# APX_USB_HUB.net
KiCad netlist of a schematic drawn in EasyEDA
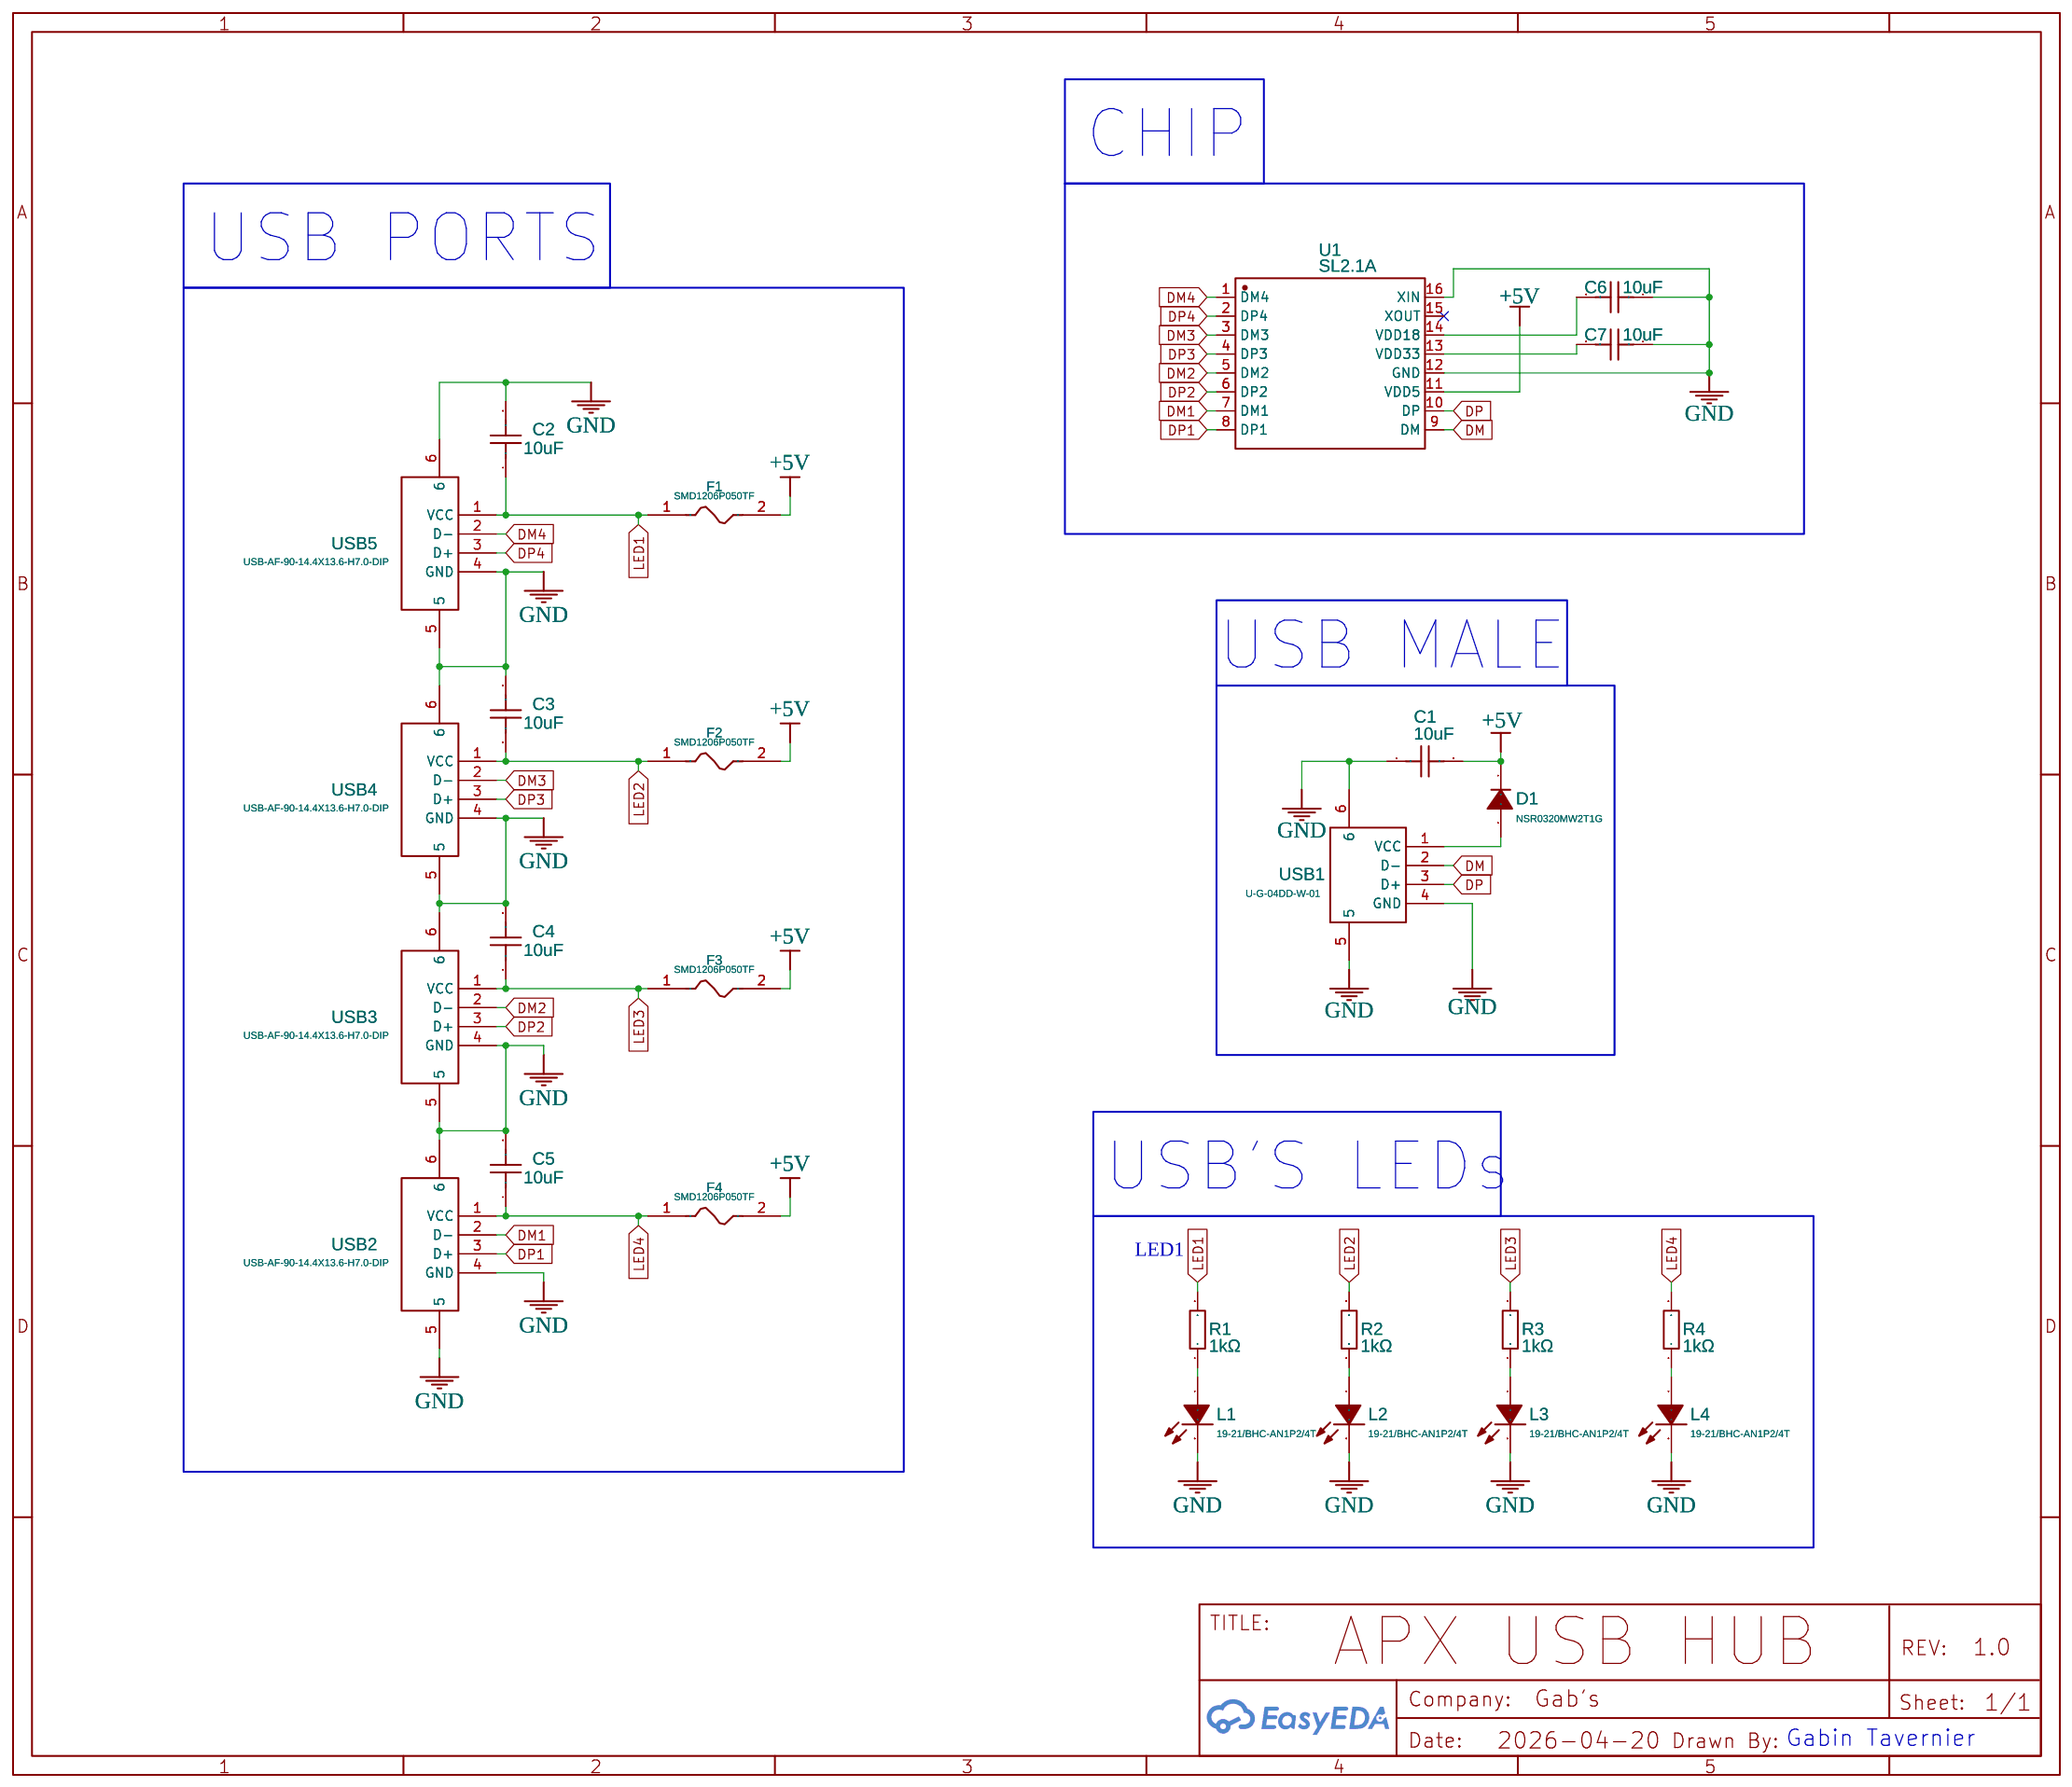
[diagram p0: schematic sheet]

(export (version "E")
  (design (tool "Eeschema 10.0.6"))
  (components
    (comp (ref "C1")
      (value "10uF")
      (fields
        (field (name "Manufacturer Part") "CL10A106KP8NNNC")
        (field (name "Manufacturer") "SAMSUNG(三星)")
      )
      (libsource (lib "") (part "CL10A106KP8NNNC_2"))
    )
    (comp (ref "C2")
      (value "10uF")
      (fields
        (field (name "Manufacturer Part") "CL10A106KP8NNNC")
        (field (name "Manufacturer") "SAMSUNG(三星)")
      )
      (libsource (lib "") (part "CL10A106KP8NNNC"))
    )
    (comp (ref "C3")
      (value "10uF")
      (fields
        (field (name "Manufacturer Part") "CL10A106KP8NNNC")
        (field (name "Manufacturer") "SAMSUNG(三星)")
      )
      (libsource (lib "") (part "CL10A106KP8NNNC"))
    )
    (comp (ref "C4")
      (value "10uF")
      (fields
        (field (name "Manufacturer Part") "CL10A106KP8NNNC")
        (field (name "Manufacturer") "SAMSUNG(三星)")
      )
      (libsource (lib "") (part "CL10A106KP8NNNC"))
    )
    (comp (ref "C5")
      (value "10uF")
      (fields
        (field (name "Manufacturer Part") "CL10A106KP8NNNC")
        (field (name "Manufacturer") "SAMSUNG(三星)")
      )
      (libsource (lib "") (part "CL10A106KP8NNNC"))
    )
    (comp (ref "C6")
      (value "10uF")
      (fields
        (field (name "Manufacturer Part") "CL10A106KP8NNNC")
        (field (name "Manufacturer") "SAMSUNG(三星)")
      )
      (libsource (lib "") (part "CL10A106KP8NNNC_1"))
    )
    (comp (ref "C7")
      (value "10uF")
      (fields
        (field (name "Manufacturer Part") "CL10A106KP8NNNC")
        (field (name "Manufacturer") "SAMSUNG(三星)")
      )
      (libsource (lib "") (part "CL10A106KP8NNNC_1"))
    )
    (comp (ref "D1")
      (value "NSR0320MW2T1G")
      (fields (field (name "Manufacturer") "onsemi(安森美)"))
      (libsource (lib "") (part "NSR0320MW2T1G"))
    )
    (comp (ref "F1")
      (value "SMD1206P050TF")
      (fields (field (name "Manufacturer") "RUILON(瑞隆源)"))
      (libsource (lib "") (part "SMD1206P050TF"))
    )
    (comp (ref "F2")
      (value "SMD1206P050TF")
      (fields (field (name "Manufacturer") "RUILON(瑞隆源)"))
      (libsource (lib "") (part "SMD1206P050TF"))
    )
    (comp (ref "F3")
      (value "SMD1206P050TF")
      (fields (field (name "Manufacturer") "RUILON(瑞隆源)"))
      (libsource (lib "") (part "SMD1206P050TF"))
    )
    (comp (ref "F4")
      (value "SMD1206P050TF")
      (fields (field (name "Manufacturer") "RUILON(瑞隆源)"))
      (libsource (lib "") (part "SMD1206P050TF"))
    )
    (comp (ref "L1")
      (value "19-21/BHC-AN1P2/4T")
      (fields (field (name "Manufacturer") "EVERLIGHT(亿光)"))
      (libsource (lib "") (part "19-21/BHC-AN1P2/4T"))
    )
    (comp (ref "L2")
      (value "19-21/BHC-AN1P2/4T")
      (fields (field (name "Manufacturer") "EVERLIGHT(亿光)"))
      (libsource (lib "") (part "19-21/BHC-AN1P2/4T"))
    )
    (comp (ref "L3")
      (value "19-21/BHC-AN1P2/4T")
      (fields (field (name "Manufacturer") "EVERLIGHT(亿光)"))
      (libsource (lib "") (part "19-21/BHC-AN1P2/4T"))
    )
    (comp (ref "L4")
      (value "19-21/BHC-AN1P2/4T")
      (fields (field (name "Manufacturer") "EVERLIGHT(亿光)"))
      (libsource (lib "") (part "19-21/BHC-AN1P2/4T"))
    )
    (comp (ref "R1")
      (value "1kΩ")
      (fields (field (name "Manufacturer Part") "RC0805FR-071KL") (field (name "Manufacturer") "YAGEO(国巨)"))
      (libsource (lib "") (part "RC0805FR-071KL"))
    )
    (comp (ref "R2")
      (value "1kΩ")
      (fields (field (name "Manufacturer Part") "RC0805FR-071KL") (field (name "Manufacturer") "YAGEO(国巨)"))
      (libsource (lib "") (part "RC0805FR-071KL"))
    )
    (comp (ref "R3")
      (value "1kΩ")
      (fields (field (name "Manufacturer Part") "RC0805FR-071KL") (field (name "Manufacturer") "YAGEO(国巨)"))
      (libsource (lib "") (part "RC0805FR-071KL"))
    )
    (comp (ref "R4")
      (value "1kΩ")
      (fields (field (name "Manufacturer Part") "RC0805FR-071KL") (field (name "Manufacturer") "YAGEO(国巨)"))
      (libsource (lib "") (part "RC0805FR-071KL"))
    )
    (comp (ref "U1")
      (value "SL2.1A")
      (fields (field (name "Manufacturer") "CoreChips(和芯润德)"))
      (libsource (lib "") (part "SL2.1A"))
    )
    (comp (ref "USB1")
      (value "U-G-04DD-W-01")
      (fields (field (name "Manufacturer Part") "U-G-O4DD-W-1") (field (name "Manufacturer") "韩国韩荣"))
      (libsource (lib "") (part "U-G-04DD-W-01"))
    )
    (comp (ref "USB2")
      (value "USB-AF-90-14.4X13.6-H7.0-DIP")
      (fields (field (name "Manufacturer Part") "903-131A1011D10100") (field (name "Manufacturer") "精拓金"))
      (libsource (lib "") (part "USB-AF-90-14.4X13.6-H7.0-DIP"))
    )
    (comp (ref "USB3")
      (value "USB-AF-90-14.4X13.6-H7.0-DIP")
      (fields (field (name "Manufacturer Part") "903-131A1011D10100") (field (name "Manufacturer") "精拓金"))
      (libsource (lib "") (part "USB-AF-90-14.4X13.6-H7.0-DIP"))
    )
    (comp (ref "USB4")
      (value "USB-AF-90-14.4X13.6-H7.0-DIP")
      (fields (field (name "Manufacturer Part") "903-131A1011D10100") (field (name "Manufacturer") "精拓金"))
      (libsource (lib "") (part "USB-AF-90-14.4X13.6-H7.0-DIP"))
    )
    (comp (ref "USB5")
      (value "USB-AF-90-14.4X13.6-H7.0-DIP")
      (fields (field (name "Manufacturer Part") "903-131A1011D10100") (field (name "Manufacturer") "精拓金"))
      (libsource (lib "") (part "USB-AF-90-14.4X13.6-H7.0-DIP"))
    )
  )
  (nets
    (net (code "1") (name "+5V") (class "Default")
      (node (ref "C1") (pin "2") (pinfunction "2_2") (pintype "unspecified"))
      (node (ref "D1") (pin "1") (pinfunction "C_1") (pintype "unspecified"))
      (node (ref "F1") (pin "2") (pinfunction "2_2") (pintype "unspecified"))
      (node (ref "F2") (pin "2") (pinfunction "2_2") (pintype "unspecified"))
      (node (ref "F3") (pin "2") (pinfunction "2_2") (pintype "unspecified"))
      (node (ref "F4") (pin "2") (pinfunction "2_2") (pintype "unspecified"))
      (node (ref "U1") (pin "11") (pinfunction "VDD5_11") (pintype "unspecified"))
    )
    (net (code "2") (name "DM") (class "Default")
      (node (ref "U1") (pin "9") (pinfunction "DM_9") (pintype "unspecified"))
      (node (ref "USB1") (pin "2") (pinfunction "D-_2") (pintype "unspecified"))
    )
    (net (code "3") (name "DM1") (class "Default")
      (node (ref "U1") (pin "7") (pinfunction "DM1_7") (pintype "unspecified"))
      (node (ref "USB2") (pin "2") (pinfunction "D-_2") (pintype "unspecified"))
    )
    (net (code "4") (name "DM2") (class "Default")
      (node (ref "U1") (pin "5") (pinfunction "DM2_5") (pintype "unspecified"))
      (node (ref "USB3") (pin "2") (pinfunction "D-_2") (pintype "unspecified"))
    )
    (net (code "5") (name "DM3") (class "Default")
      (node (ref "U1") (pin "3") (pinfunction "DM3_3") (pintype "unspecified"))
      (node (ref "USB4") (pin "2") (pinfunction "D-_2") (pintype "unspecified"))
    )
    (net (code "6") (name "DM4") (class "Default")
      (node (ref "U1") (pin "1") (pinfunction "DM4_1") (pintype "unspecified"))
      (node (ref "USB5") (pin "2") (pinfunction "D-_2") (pintype "unspecified"))
    )
    (net (code "7") (name "DP") (class "Default")
      (node (ref "U1") (pin "10") (pinfunction "DP_10") (pintype "unspecified"))
      (node (ref "USB1") (pin "3") (pinfunction "D+_3") (pintype "unspecified"))
    )
    (net (code "8") (name "DP1") (class "Default")
      (node (ref "U1") (pin "8") (pinfunction "DP1_8") (pintype "unspecified"))
      (node (ref "USB2") (pin "3") (pinfunction "D+_3") (pintype "unspecified"))
    )
    (net (code "9") (name "DP2") (class "Default")
      (node (ref "U1") (pin "6") (pinfunction "DP2_6") (pintype "unspecified"))
      (node (ref "USB3") (pin "3") (pinfunction "D+_3") (pintype "unspecified"))
    )
    (net (code "10") (name "DP3") (class "Default")
      (node (ref "U1") (pin "4") (pinfunction "DP3_4") (pintype "unspecified"))
      (node (ref "USB4") (pin "3") (pinfunction "D+_3") (pintype "unspecified"))
    )
    (net (code "11") (name "DP4") (class "Default")
      (node (ref "U1") (pin "2") (pinfunction "DP4_2") (pintype "unspecified"))
      (node (ref "USB5") (pin "3") (pinfunction "D+_3") (pintype "unspecified"))
    )
    (net (code "12") (name "GND") (class "Default")
      (node (ref "C1") (pin "1") (pinfunction "1_1") (pintype "unspecified"))
      (node (ref "C2") (pin "2") (pinfunction "2_2") (pintype "unspecified"))
      (node (ref "C3") (pin "2") (pinfunction "2_2") (pintype "unspecified"))
      (node (ref "C4") (pin "2") (pinfunction "2_2") (pintype "unspecified"))
      (node (ref "C5") (pin "2") (pinfunction "2_2") (pintype "unspecified"))
      (node (ref "C6") (pin "1") (pinfunction "1_1") (pintype "unspecified"))
      (node (ref "C7") (pin "1") (pinfunction "1_1") (pintype "unspecified"))
      (node (ref "L1") (pin "2") (pinfunction "K_2") (pintype "unspecified"))
      (node (ref "L2") (pin "2") (pinfunction "K_2") (pintype "unspecified"))
      (node (ref "L3") (pin "2") (pinfunction "K_2") (pintype "unspecified"))
      (node (ref "L4") (pin "2") (pinfunction "K_2") (pintype "unspecified"))
      (node (ref "U1") (pin "12") (pinfunction "GND_12") (pintype "unspecified"))
      (node (ref "U1") (pin "16") (pinfunction "XIN_16") (pintype "unspecified"))
      (node (ref "USB1") (pin "4") (pinfunction "GND_4") (pintype "unspecified"))
      (node (ref "USB1") (pin "5") (pinfunction "5_5") (pintype "unspecified"))
      (node (ref "USB1") (pin "6") (pinfunction "6_6") (pintype "unspecified"))
      (node (ref "USB2") (pin "4") (pinfunction "GND_4") (pintype "unspecified"))
      (node (ref "USB2") (pin "5") (pinfunction "5_5") (pintype "unspecified"))
      (node (ref "USB2") (pin "6") (pinfunction "6_6") (pintype "unspecified"))
      (node (ref "USB3") (pin "4") (pinfunction "GND_4") (pintype "unspecified"))
      (node (ref "USB3") (pin "5") (pinfunction "5_5") (pintype "unspecified"))
      (node (ref "USB3") (pin "6") (pinfunction "6_6") (pintype "unspecified"))
      (node (ref "USB4") (pin "4") (pinfunction "GND_4") (pintype "unspecified"))
      (node (ref "USB4") (pin "5") (pinfunction "5_5") (pintype "unspecified"))
      (node (ref "USB4") (pin "6") (pinfunction "6_6") (pintype "unspecified"))
      (node (ref "USB5") (pin "4") (pinfunction "GND_4") (pintype "unspecified"))
      (node (ref "USB5") (pin "5") (pinfunction "5_5") (pintype "unspecified"))
      (node (ref "USB5") (pin "6") (pinfunction "6_6") (pintype "unspecified"))
    )
    (net (code "13") (name "LED1") (class "Default")
      (node (ref "C2") (pin "1") (pinfunction "1_1") (pintype "unspecified"))
      (node (ref "F1") (pin "1") (pinfunction "1_1") (pintype "unspecified"))
      (node (ref "R1") (pin "2") (pinfunction "2_2") (pintype "input"))
      (node (ref "USB5") (pin "1") (pinfunction "VCC_1") (pintype "unspecified"))
    )
    (net (code "14") (name "LED2") (class "Default")
      (node (ref "C3") (pin "1") (pinfunction "1_1") (pintype "unspecified"))
      (node (ref "F2") (pin "1") (pinfunction "1_1") (pintype "unspecified"))
      (node (ref "R2") (pin "2") (pinfunction "2_2") (pintype "input"))
      (node (ref "USB4") (pin "1") (pinfunction "VCC_1") (pintype "unspecified"))
    )
    (net (code "15") (name "LED3") (class "Default")
      (node (ref "C4") (pin "1") (pinfunction "1_1") (pintype "unspecified"))
      (node (ref "F3") (pin "1") (pinfunction "1_1") (pintype "unspecified"))
      (node (ref "R3") (pin "2") (pinfunction "2_2") (pintype "input"))
      (node (ref "USB3") (pin "1") (pinfunction "VCC_1") (pintype "unspecified"))
    )
    (net (code "16") (name "LED4") (class "Default")
      (node (ref "C5") (pin "1") (pinfunction "1_1") (pintype "unspecified"))
      (node (ref "F4") (pin "1") (pinfunction "1_1") (pintype "unspecified"))
      (node (ref "R4") (pin "2") (pinfunction "2_2") (pintype "input"))
      (node (ref "USB2") (pin "1") (pinfunction "VCC_1") (pintype "unspecified"))
    )
    (net (code "17") (name "Net-(D1-A)") (class "Default")
      (node (ref "D1") (pin "2") (pinfunction "A_2") (pintype "unspecified"))
      (node (ref "USB1") (pin "1") (pinfunction "VCC_1") (pintype "unspecified"))
    )
    (net (code "18") (name "Net-(L1-A)") (class "Default")
      (node (ref "L1") (pin "1") (pinfunction "A_1") (pintype "unspecified"))
      (node (ref "R1") (pin "1") (pinfunction "1_1") (pintype "input"))
    )
    (net (code "19") (name "Net-(L2-A)") (class "Default")
      (node (ref "L2") (pin "1") (pinfunction "A_1") (pintype "unspecified"))
      (node (ref "R2") (pin "1") (pinfunction "1_1") (pintype "input"))
    )
    (net (code "20") (name "Net-(L3-A)") (class "Default")
      (node (ref "L3") (pin "1") (pinfunction "A_1") (pintype "unspecified"))
      (node (ref "R3") (pin "1") (pinfunction "1_1") (pintype "input"))
    )
    (net (code "21") (name "Net-(L4-A)") (class "Default")
      (node (ref "L4") (pin "1") (pinfunction "A_1") (pintype "unspecified"))
      (node (ref "R4") (pin "1") (pinfunction "1_1") (pintype "input"))
    )
    (net (code "22") (name "Net-(U1-VDD18)") (class "Default")
      (node (ref "C6") (pin "2") (pinfunction "2_2") (pintype "unspecified"))
      (node (ref "U1") (pin "14") (pinfunction "VDD18_14") (pintype "unspecified"))
    )
    (net (code "23") (name "Net-(U1-VDD33)") (class "Default")
      (node (ref "C7") (pin "2") (pinfunction "2_2") (pintype "unspecified"))
      (node (ref "U1") (pin "13") (pinfunction "VDD33_13") (pintype "unspecified"))
    )
    (net (code "24") (name "unconnected-(U1-XOUT-Pad15)") (class "Default")
      (node (ref "U1") (pin "15") (pinfunction "XOUT_15") (pintype "unspecified+no_connect"))
    )
  )
)
